# power_supply.net
KiCad netlist of a schematic drawn in EasyEDA Pro
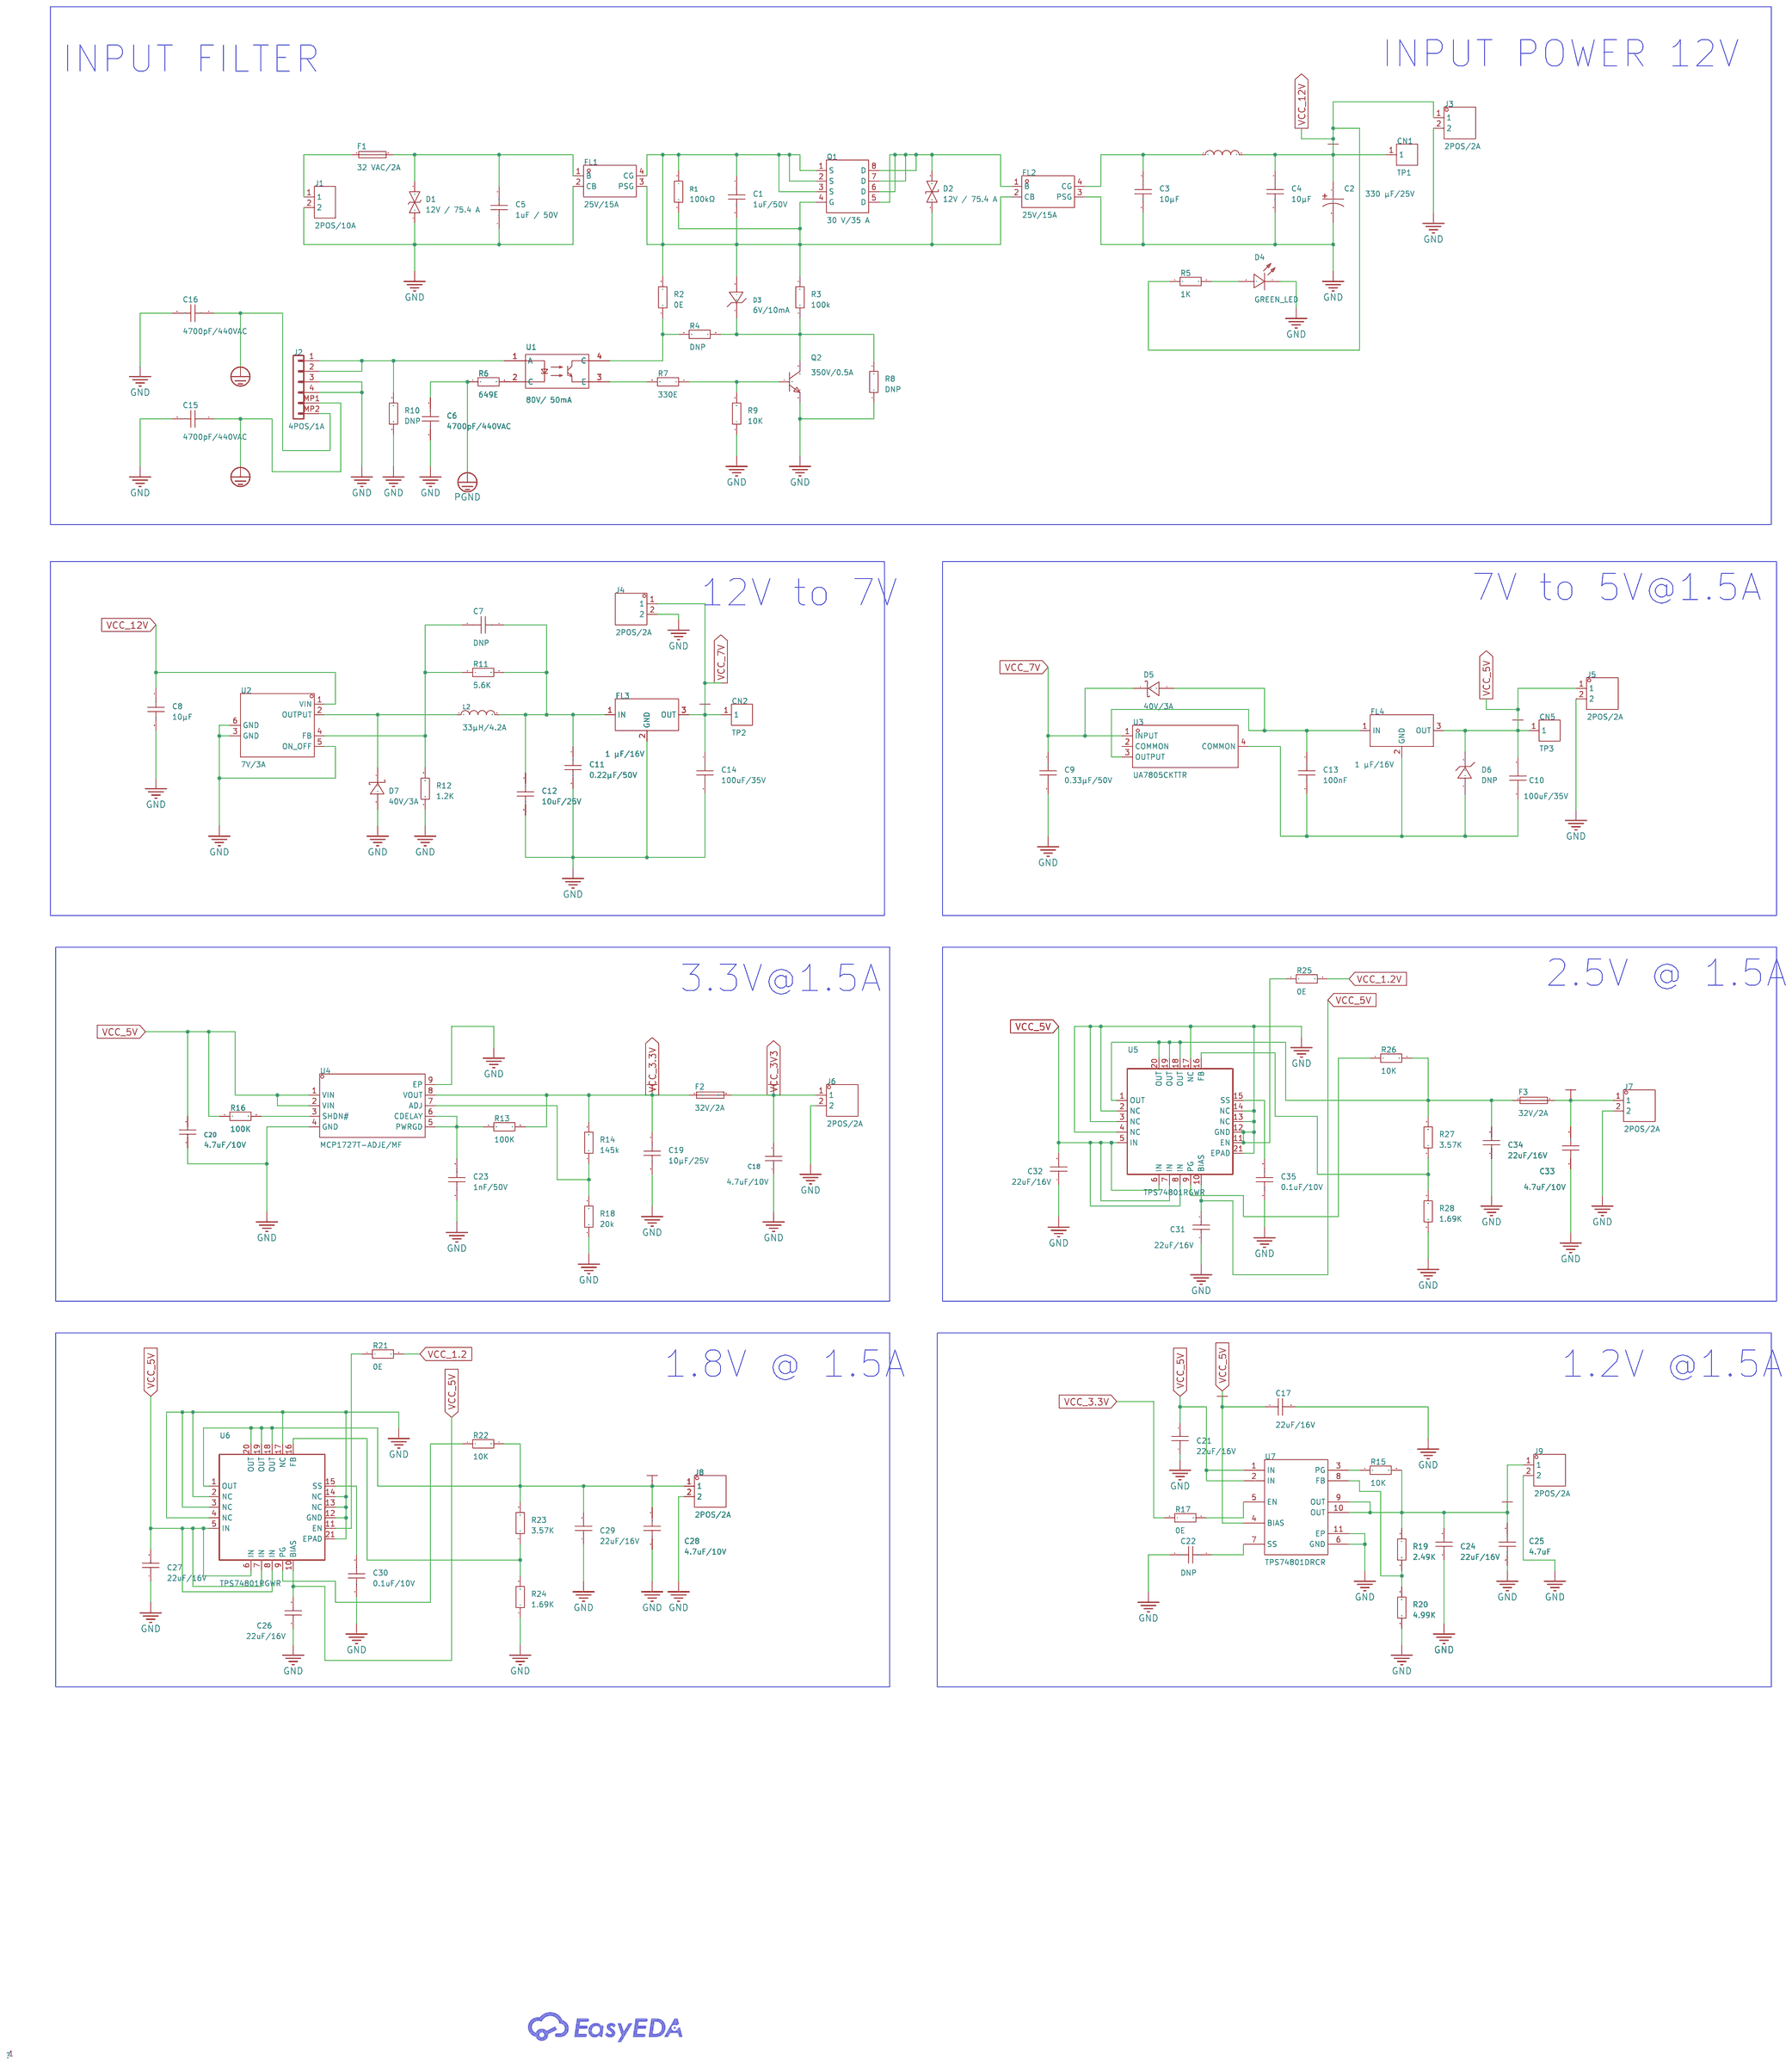
[diagram p0: schematic sheet]

(export (version "E")
  (design (tool "Eeschema 10.0.6"))
  (components
    (comp (ref "C1")
      (value "1uF/50V")
      (footprint "easyedapro:C0603")
      (libsource (lib "easyedapro") (part "CAP"))
    )
    (comp (ref "C2")
      (value "330 µF/25V")
      (footprint "easyedapro:CAP-SMD_BD10.0-L10.3-W10.3-FD")
      (fields (field (name "Manufacturer Part") "EEHZA1E331P") (field (name "Manufacturer") "PANASONIC(松下)"))
      (libsource (lib "easyedapro") (part "EEHZA1E331P"))
    )
    (comp (ref "C3")
      (value "10µF")
      (footprint "easyedapro:C0603")
      (libsource (lib "easyedapro") (part "CAP"))
    )
    (comp (ref "C4")
      (value "10µF")
      (footprint "easyedapro:C0603")
      (libsource (lib "easyedapro") (part "CAP"))
    )
    (comp (ref "C5")
      (value "1uF / 50V")
      (footprint "easyedapro:C0402")
      (description "Capacitance:100nF Tolerance:±10% Tolerance:±10% Voltage Rating:16V Temperature Coefficient:X7R")
      (fields
        (field (name "Manufacturer Part") "CL05B104KO5NNNC")
        (field (name "Manufacturer") "SAMSUNG(三星)")
      )
      (libsource (lib "easyedapro") (part "CL05B104KO5NNNC"))
    )
    (comp (ref "C6")
      (value "4700pF/440VAC")
      (footprint "easyedapro:CAP-TH_L11.0-W5.0-P10.00-D0.7")
      (fields
        (field (name "Manufacturer Part") "C947U472MZVDBA7317")
        (field (name "Manufacturer") "KEMET(基美)")
      )
      (libsource (lib "easyedapro") (part "C947U472MZVDBA7317"))
    )
    (comp (ref "C7") (value "DNP") (footprint "easyedapro:C0603") (libsource (lib "easyedapro") (part "CAP")))
    (comp (ref "C8")
      (value "10µF")
      (footprint "easyedapro:C0603")
      (libsource (lib "easyedapro") (part "CAP"))
    )
    (comp (ref "C9")
      (value "0.33µF/50V")
      (footprint "easyedapro:C0603")
      (libsource (lib "easyedapro") (part "CAP"))
    )
    (comp (ref "C10")
      (value "100uF/35V")
      (footprint "easyedapro:C0603")
      (libsource (lib "easyedapro") (part "CAP"))
    )
    (comp (ref "C11")
      (value "0.22µF/50V")
      (footprint "easyedapro:C0603")
      (libsource (lib "easyedapro") (part "CAP"))
    )
    (comp (ref "C12")
      (value "10uF/25V")
      (footprint "easyedapro:C0603")
      (libsource (lib "easyedapro") (part "CAP"))
    )
    (comp (ref "C13")
      (value "100nF")
      (footprint "easyedapro:C0603")
      (libsource (lib "easyedapro") (part "CAP"))
    )
    (comp (ref "C14")
      (value "100uF/35V")
      (footprint "easyedapro:C0603")
      (libsource (lib "easyedapro") (part "CAP"))
    )
    (comp (ref "C15")
      (value "4700pF/440VAC")
      (footprint "easyedapro:C0603")
      (libsource (lib "easyedapro") (part "CAP"))
    )
    (comp (ref "C16")
      (value "4700pF/440VAC")
      (footprint "easyedapro:C0603")
      (libsource (lib "easyedapro") (part "CAP"))
    )
    (comp (ref "C17")
      (value "22uF/16V")
      (footprint "easyedapro:C0805")
      (description "容值:22uF;精度:±20%;额定电压:16V;材质(温度系数):X5R;")
      (fields
        (field (name "Manufacturer Part") "CL21A226MOQNNNE")
        (field (name "Manufacturer") "SAMSUNG(三星)")
      )
      (libsource (lib "easyedapro") (part "CL21A226MOQNNNE"))
    )
    (comp (ref "C18")
      (value "4.7uF/10V")
      (footprint "easyedapro:C0603")
      (description "Capacitance:4.7uF Tolerance:±10% Tolerance:±10% Voltage Rating:10V Temperature Coefficient:X5R")
      (fields
        (field (name "Manufacturer Part") "CL10A475KP8NNNC")
        (field (name "Manufacturer") "SAMSUNG(三星)")
      )
      (libsource (lib "easyedapro") (part "CL10A475KP8NNNC"))
    )
    (comp (ref "C19")
      (value "10µF/25V")
      (footprint "easyedapro:C0603")
      (libsource (lib "easyedapro") (part "CAP"))
    )
    (comp (ref "C20")
      (value "4.7uF/10V")
      (footprint "easyedapro:C0603")
      (description "Capacitance:4.7uF Tolerance:±10% Tolerance:±10% Voltage Rating:10V Temperature Coefficient:X5R")
      (fields
        (field (name "Manufacturer Part") "CL10A475KP8NNNC")
        (field (name "Manufacturer") "SAMSUNG(三星)")
      )
      (libsource (lib "easyedapro") (part "CL10A475KP8NNNC"))
    )
    (comp (ref "C21")
      (value "22uF/16V")
      (footprint "easyedapro:C0805")
      (description "容值:22uF;精度:±20%;额定电压:16V;材质(温度系数):X5R;")
      (fields
        (field (name "Manufacturer Part") "CL21A226MOQNNNE")
        (field (name "Manufacturer") "SAMSUNG(三星)")
      )
      (libsource (lib "easyedapro") (part "CL21A226MOQNNNE"))
    )
    (comp (ref "C22")
      (value "DNP")
      (footprint "easyedapro:C0402")
      (fields
        (field (name "Manufacturer Part") "CC0402JRX7R6BB104")
        (field (name "Manufacturer") "YAGEO(国巨)")
      )
      (libsource (lib "easyedapro") (part "CC0402JRX7R6BB104"))
    )
    (comp (ref "C23")
      (value "1nF/50V")
      (footprint "easyedapro:C0402")
      (description "Capacitance:1nF Tolerance:±5% Tolerance:±5% Voltage Rating:50V Temperature Coefficient:C0G")
      (fields
        (field (name "Manufacturer Part") "GRM1555C1H102JA01D")
        (field (name "Manufacturer") "muRata(村田)")
      )
      (libsource (lib "easyedapro") (part "GRM1555C1H102JA01D"))
    )
    (comp (ref "C24")
      (value "22uF/16V")
      (footprint "easyedapro:C0805")
      (description "容值:22uF;精度:±20%;额定电压:16V;材质(温度系数):X5R;")
      (fields
        (field (name "Manufacturer Part") "CL21A226MOQNNNE")
        (field (name "Manufacturer") "SAMSUNG(三星)")
      )
      (libsource (lib "easyedapro") (part "CL21A226MOQNNNE"))
    )
    (comp (ref "C25")
      (value "4.7uF")
      (footprint "easyedapro:C0603")
      (libsource (lib "easyedapro") (part "CAP"))
    )
    (comp (ref "C26")
      (value "22uF/16V")
      (footprint "easyedapro:C0805")
      (description "容值:22uF;精度:±20%;额定电压:16V;材质(温度系数):X5R;")
      (fields
        (field (name "Manufacturer Part") "CL21A226MOQNNNE")
        (field (name "Manufacturer") "SAMSUNG(三星)")
      )
      (libsource (lib "easyedapro") (part "CL21A226MOQNNNE"))
    )
    (comp (ref "C27")
      (value "22uF/16V")
      (footprint "easyedapro:C0805")
      (description "容值:22uF;精度:±20%;额定电压:16V;材质(温度系数):X5R;")
      (fields
        (field (name "Manufacturer Part") "CL21A226MOQNNNE")
        (field (name "Manufacturer") "SAMSUNG(三星)")
      )
      (libsource (lib "easyedapro") (part "CL21A226MOQNNNE"))
    )
    (comp (ref "C28")
      (value "4.7uF/10V")
      (footprint "easyedapro:C0603")
      (libsource (lib "easyedapro") (part "CAP"))
    )
    (comp (ref "C29")
      (value "22uF/16V")
      (footprint "easyedapro:C0805")
      (description "容值:22uF;精度:±20%;额定电压:16V;材质(温度系数):X5R;")
      (fields
        (field (name "Manufacturer Part") "CL21A226MOQNNNE")
        (field (name "Manufacturer") "SAMSUNG(三星)")
      )
      (libsource (lib "easyedapro") (part "CL21A226MOQNNNE"))
    )
    (comp (ref "C30")
      (value "0.1uF/10V")
      (footprint "easyedapro:C0402")
      (fields
        (field (name "Manufacturer Part") "CC0402JRX7R6BB104")
        (field (name "Manufacturer") "YAGEO(国巨)")
      )
      (libsource (lib "easyedapro") (part "CC0402JRX7R6BB104"))
    )
    (comp (ref "C31")
      (value "22uF/16V")
      (footprint "easyedapro:C0805")
      (description "容值:22uF;精度:±20%;额定电压:16V;材质(温度系数):X5R;")
      (fields
        (field (name "Manufacturer Part") "CL21A226MOQNNNE")
        (field (name "Manufacturer") "SAMSUNG(三星)")
      )
      (libsource (lib "easyedapro") (part "CL21A226MOQNNNE"))
    )
    (comp (ref "C32")
      (value "22uF/16V")
      (footprint "easyedapro:C0805")
      (description "容值:22uF;精度:±20%;额定电压:16V;材质(温度系数):X5R;")
      (fields
        (field (name "Manufacturer Part") "CL21A226MOQNNNE")
        (field (name "Manufacturer") "SAMSUNG(三星)")
      )
      (libsource (lib "easyedapro") (part "CL21A226MOQNNNE"))
    )
    (comp (ref "C33")
      (value "4.7uF/10V")
      (footprint "easyedapro:C0603")
      (libsource (lib "easyedapro") (part "CAP"))
    )
    (comp (ref "C34")
      (value "22uF/16V")
      (footprint "easyedapro:C0805")
      (description "容值:22uF;精度:±20%;额定电压:16V;材质(温度系数):X5R;")
      (fields
        (field (name "Manufacturer Part") "CL21A226MOQNNNE")
        (field (name "Manufacturer") "SAMSUNG(三星)")
      )
      (libsource (lib "easyedapro") (part "CL21A226MOQNNNE"))
    )
    (comp (ref "C35")
      (value "0.1uF/10V")
      (footprint "easyedapro:C0402")
      (fields
        (field (name "Manufacturer Part") "CC0402JRX7R6BB104")
        (field (name "Manufacturer") "YAGEO(国巨)")
      )
      (libsource (lib "easyedapro") (part "CC0402JRX7R6BB104"))
    )
    (comp (ref "CN1")
      (value "TP1")
      (footprint "easyedapro:CONN-SMD_5017")
      (libsource (lib "easyedapro") (part "5017_C9900015874"))
    )
    (comp (ref "CN2")
      (value "TP2")
      (footprint "easyedapro:CONN-SMD_5017")
      (libsource (lib "easyedapro") (part "5017_C9900015874"))
    )
    (comp (ref "CN5")
      (value "TP3")
      (footprint "easyedapro:CONN-SMD_5017")
      (libsource (lib "easyedapro") (part "5017_C9900015874"))
    )
    (comp (ref "D1")
      (value "12V / 75.4 A")
      (footprint "easyedapro:D0402-BI")
      (fields (field (name "Manufacturer") "GOOD-ARK(固锝)"))
      (libsource (lib "easyedapro") (part "GSEPD15B0005"))
    )
    (comp (ref "D2")
      (value "12V / 75.4 A")
      (footprint "easyedapro:SMC_L6.9-W5.9-LS7.9-BI")
      (fields (field (name "Manufacturer") "R+O(宏嘉诚)"))
      (libsource (lib "easyedapro") (part "SMCJ12CA_C41411748"))
    )
    (comp (ref "D3")
      (value "6V/10mA")
      (footprint "easyedapro:SOD-123_L2.7-W1.6-LS3.7-RD")
      (fields (field (name "Manufacturer") "onsemi(安森美)"))
      (libsource (lib "easyedapro") (part "MMSZ5233BT1G"))
    )
    (comp (ref "D4")
      (value "GREEN_LED")
      (footprint "easyedapro:LED0603-RD")
      (fields (field (name "Manufacturer") "LITEON(光宝)"))
      (libsource (lib "easyedapro") (part "LTST-C190KGKT"))
    )
    (comp (ref "D5")
      (value "40V/3A")
      (footprint "easyedapro:SOD-128_L3.7-W2.5-LS4.7-RD")
      (fields (field (name "Manufacturer") "Nexperia(安世)"))
      (libsource (lib "easyedapro") (part "PMEG40T30EPX"))
    )
    (comp (ref "D6")
      (value "DNP")
      (footprint "easyedapro:SOD-123_L2.8-W1.8-LS3.7-RD")
      (fields (field (name "Manufacturer") "DIODES(美台)"))
      (libsource (lib "easyedapro") (part "MMSZ5231B-7-F"))
    )
    (comp (ref "D7")
      (value "40V/3A")
      (footprint "easyedapro:SOD-128_L3.7-W2.5-LS4.7-RD")
      (fields (field (name "Manufacturer") "Nexperia(安世)"))
      (libsource (lib "easyedapro") (part "PMEG40T30EPX"))
    )
    (comp (ref "F1")
      (value "32 VAC/2A")
      (footprint "easyedapro:FUSE-SMD_L20.0-W5.2")
      (fields (field (name "Manufacturer") "SET(赛尔特)"))
      (libsource (lib "easyedapro") (part "FUSE SGT520-8A"))
    )
    (comp (ref "F2")
      (value "32V/2A")
      (footprint "easyedapro:F0402")
      (fields (field (name "Manufacturer") "PANASONIC(松下)"))
      (libsource (lib "easyedapro") (part "ERBRD2R00X"))
    )
    (comp (ref "F3")
      (value "32V/2A")
      (footprint "easyedapro:F0402")
      (fields (field (name "Manufacturer") "PANASONIC(松下)"))
      (libsource (lib "easyedapro") (part "ERBRD2R00X"))
    )
    (comp (ref "FL1")
      (value "25V/15A")
      (footprint "easyedapro:FILTER-TH_6P-L12.0-W11.0_BNX016-01")
      (fields (field (name "Manufacturer Part") "BNX016-01") (field (name "Manufacturer") "muRata(村田)"))
      (libsource (lib "easyedapro") (part "BNX016-01"))
    )
    (comp (ref "FL2")
      (value "25V/15A")
      (footprint "easyedapro:FILTER-TH_6P-L12.0-W11.0_BNX016-01")
      (fields (field (name "Manufacturer Part") "BNX016-01") (field (name "Manufacturer") "muRata(村田)"))
      (libsource (lib "easyedapro") (part "BNX016-01"))
    )
    (comp (ref "FL3")
      (value "1 µF/16V")
      (footprint "easyedapro:FILTER-SMD_3P-L2.0-W1.2-L")
      (fields (field (name "Manufacturer") "muRata(村田)"))
      (libsource (lib "easyedapro") (part "NFM21PC105B1C3D"))
    )
    (comp (ref "FL4")
      (value "1 µF/16V")
      (footprint "easyedapro:FILTER-SMD_3P-L2.0-W1.2-L")
      (fields (field (name "Manufacturer") "muRata(村田)"))
      (libsource (lib "easyedapro") (part "NFM21PC105B1C3D"))
    )
    (comp (ref "J1")
      (value "2POS/10A")
      (footprint "easyedapro:CONN-TH_2P-P3.96-V")
      (fields (field (name "Manufacturer") "JST"))
      (libsource (lib "easyedapro") (part "B2P-VH-GZ"))
    )
    (comp (ref "J2")
      (value "Molex_PicoBlade_1x4_0533980471")
      (footprint "easyedapro:antmicro-footprints:Conn_Molex_PicoBlade_1x4_0533980471")
      (libsource (lib "easyedapro") (part "antmicroWire2BoardConnectors_Molex_PicoBlade_1x4_0533980471"))
    )
    (comp (ref "J3")
      (value "2POS/2A")
      (footprint "easyedapro:CONN-TH_S2B-PH-K-S-GW")
      (fields (field (name "Manufacturer") "JST"))
      (libsource (lib "easyedapro") (part "S2B-PH-K-S-GW"))
    )
    (comp (ref "J4")
      (value "2POS/2A")
      (footprint "easyedapro:CONN-TH_S2B-PH-K-S-GW")
      (fields (field (name "Manufacturer") "JST"))
      (libsource (lib "easyedapro") (part "S2B-PH-K-S-GW"))
    )
    (comp (ref "J5")
      (value "2POS/2A")
      (footprint "easyedapro:CONN-TH_S2B-PH-K-S-GW")
      (fields (field (name "Manufacturer") "JST"))
      (libsource (lib "easyedapro") (part "S2B-PH-K-S-GW"))
    )
    (comp (ref "J6")
      (value "2POS/2A")
      (footprint "easyedapro:CONN-TH_S2B-PH-K-S-GW")
      (fields (field (name "Manufacturer") "JST"))
      (libsource (lib "easyedapro") (part "S2B-PH-K-S-GW"))
    )
    (comp (ref "J7")
      (value "2POS/2A")
      (footprint "easyedapro:CONN-TH_S2B-PH-K-S-GW")
      (fields (field (name "Manufacturer") "JST"))
      (libsource (lib "easyedapro") (part "S2B-PH-K-S-GW"))
    )
    (comp (ref "J8")
      (value "2POS/2A")
      (footprint "easyedapro:CONN-TH_S2B-PH-K-S-GW")
      (fields (field (name "Manufacturer") "JST"))
      (libsource (lib "easyedapro") (part "S2B-PH-K-S-GW"))
    )
    (comp (ref "J9")
      (value "2POS/2A")
      (footprint "easyedapro:CONN-TH_S2B-PH-K-S-GW")
      (fields (field (name "Manufacturer") "JST"))
      (libsource (lib "easyedapro") (part "S2B-PH-K-S-GW"))
    )
    (comp (ref "L1")
      (value "22uH")
      (footprint "easyedapro:7447709220")
      (fields (field (name "Manufacturer Part") "22µH/5.3A") (field (name "Manufacturer") "WURTH"))
      (libsource (lib "easyedapro") (part "7447709220"))
    )
    (comp (ref "L2")
      (value "33µH/4.2A")
      (footprint "easyedapro:IND-SMD_L12.0-W12.0-A")
      (fields (field (name "Manufacturer Part") "7447709330") (field (name "Manufacturer") "Wurth(伍尔特)"))
      (libsource (lib "easyedapro") (part "7447709330"))
    )
    (comp (ref "Q1")
      (value "30 V/35 A")
      (footprint "easyedapro:POWERPAK-1212-8_L3.0-W3.0-P0.65-LS3.3-BL")
      (fields (field (name "Manufacturer") "MSKSEMI(美森科)"))
      (libsource (lib "easyedapro") (part "MSISH101DN-T1-GE3"))
    )
    (comp (ref "Q2")
      (value "350V/0.5A")
      (footprint "easyedapro:SOT-23-3_L2.9-W1.3-P1.90-LS2.4-BR")
      (fields (field (name "Manufacturer") "DIODES(美台)"))
      (libsource (lib "easyedapro") (part "FMMT6517TA"))
    )
    (comp (ref "R1")
      (value "100kΩ")
      (footprint "easyedapro:R0603")
      (fields (field (name "Manufacturer Part") "RC0603FR-07100KL") (field (name "Manufacturer") "YAGEO(国巨)"))
      (libsource (lib "easyedapro") (part "RC0603FR-07100KL"))
    )
    (comp (ref "R2") (value "0E") (footprint "easyedapro:R0603") (libsource (lib "easyedapro") (part "Res")))
    (comp (ref "R3")
      (value "100k")
      (footprint "easyedapro:R0603")
      (libsource (lib "easyedapro") (part "Res"))
    )
    (comp (ref "R4") (value "DNP") (footprint "easyedapro:R0603") (libsource (lib "easyedapro") (part "Res")))
    (comp (ref "R5") (value "1K") (footprint "easyedapro:R0603") (libsource (lib "easyedapro") (part "Res")))
    (comp (ref "R6")
      (value "649E")
      (footprint "easyedapro:R0603")
      (libsource (lib "easyedapro") (part "Res"))
    )
    (comp (ref "R7")
      (value "330E")
      (footprint "easyedapro:R0603")
      (libsource (lib "easyedapro") (part "Res"))
    )
    (comp (ref "R8") (value "DNP") (footprint "easyedapro:R0603") (libsource (lib "easyedapro") (part "Res")))
    (comp (ref "R9") (value "10K") (footprint "easyedapro:R0603") (libsource (lib "easyedapro") (part "Res")))
    (comp (ref "R10")
      (value "DNP")
      (footprint "easyedapro:R0603")
      (libsource (lib "easyedapro") (part "Res"))
    )
    (comp (ref "R11")
      (value "5.6K")
      (footprint "easyedapro:R0603")
      (libsource (lib "easyedapro") (part "Res"))
    )
    (comp (ref "R12")
      (value "1.2K")
      (footprint "easyedapro:R0603")
      (libsource (lib "easyedapro") (part "Res"))
    )
    (comp (ref "R13")
      (value "100K")
      (footprint "easyedapro:R0402")
      (fields (field (name "Manufacturer Part") "ERJ2RKF1003X") (field (name "Manufacturer") "PANASONIC(松下)"))
      (libsource (lib "easyedapro") (part "ERJ-2RKF1003X"))
    )
    (comp (ref "R14")
      (value "145k")
      (footprint "easyedapro:R0603")
      (libsource (lib "easyedapro") (part "Res"))
    )
    (comp (ref "R15")
      (value "10K")
      (footprint "easyedapro:R0603")
      (libsource (lib "easyedapro") (part "Res"))
    )
    (comp (ref "R16")
      (value "100K")
      (footprint "easyedapro:R0402")
      (fields (field (name "Manufacturer Part") "ERJ2RKF1003X") (field (name "Manufacturer") "PANASONIC(松下)"))
      (libsource (lib "easyedapro") (part "ERJ-2RKF1003X"))
    )
    (comp (ref "R17") (value "0E") (footprint "easyedapro:R0603") (libsource (lib "easyedapro") (part "Res")))
    (comp (ref "R18")
      (value "20k")
      (footprint "easyedapro:R0603")
      (libsource (lib "easyedapro") (part "Res"))
    )
    (comp (ref "R19")
      (value "2.49K")
      (footprint "easyedapro:R0603")
      (libsource (lib "easyedapro") (part "Res"))
    )
    (comp (ref "R20")
      (value "4.99K")
      (footprint "easyedapro:R0603")
      (libsource (lib "easyedapro") (part "Res"))
    )
    (comp (ref "R21") (value "0E") (footprint "easyedapro:R0603") (libsource (lib "easyedapro") (part "Res")))
    (comp (ref "R22")
      (value "10K")
      (footprint "easyedapro:R0603")
      (libsource (lib "easyedapro") (part "Res"))
    )
    (comp (ref "R23")
      (value "3.57K")
      (footprint "easyedapro:R0603")
      (libsource (lib "easyedapro") (part "Res"))
    )
    (comp (ref "R24")
      (value "1.69K")
      (footprint "easyedapro:R0603")
      (libsource (lib "easyedapro") (part "Res"))
    )
    (comp (ref "R25") (value "0E") (footprint "easyedapro:R0603") (libsource (lib "easyedapro") (part "Res")))
    (comp (ref "R26")
      (value "10K")
      (footprint "easyedapro:R0603")
      (libsource (lib "easyedapro") (part "Res"))
    )
    (comp (ref "R27")
      (value "3.57K")
      (footprint "easyedapro:R0603")
      (libsource (lib "easyedapro") (part "Res"))
    )
    (comp (ref "R28")
      (value "1.69K")
      (footprint "easyedapro:R0603")
      (libsource (lib "easyedapro") (part "Res"))
    )
    (comp (ref "U1")
      (value "80V/ 50mA")
      (footprint "easyedapro:SOP-4_L6.5-W4.6-P2.54-LS10.3-TL")
      (fields (field (name "Manufacturer") "VISHAY(威世)"))
      (libsource (lib "easyedapro") (part "VO617A-8X017T"))
    )
    (comp (ref "U2")
      (value "7V/3A")
      (footprint "easyedapro:TO-263-5_L10.4-W8.6-P1.70-LS15.3-BR")
      (libsource (lib "easyedapro") (part "LM2596S-ADJ_C3198435"))
    )
    (comp (ref "U3")
      (value "UA7805CKTTR")
      (footprint "easyedapro:TO-263-3_L10.2-W9.0-P2.54-LS15.2-TL")
      (fields (field (name "Manufacturer") "TI(德州仪器)"))
      (libsource (lib "easyedapro") (part "UA7805CKTTR"))
    )
    (comp (ref "U4")
      (value "MCP1727T-ADJE/MF")
      (footprint "easyedapro:DFN-8_L3.0-W3.0-P0.65-BL-EP")
      (fields (field (name "Manufacturer") "MICROCHIP(美国微芯)"))
      (libsource (lib "easyedapro") (part "MCP1727T-ADJE/MF"))
    )
    (comp (ref "U5")
      (value "TPS74801RGWR")
      (footprint "easyedapro:VQFN-20_L5.0-W5.0-P0.65-TL-EP")
      (fields (field (name "Manufacturer") "Texas Instruments"))
      (libsource (lib "easyedapro") (part "TPS74801RGWR"))
    )
    (comp (ref "U6")
      (value "TPS74801RGWR")
      (footprint "easyedapro:VQFN-20_L5.0-W5.0-P0.65-TL-EP")
      (fields (field (name "Manufacturer") "Texas Instruments"))
      (libsource (lib "easyedapro") (part "TPS74801RGWR"))
    )
    (comp (ref "U7")
      (value "TPS74801DRCR")
      (footprint "easyedapro:VSON-10_L3.0-W3.0-P0.50-TL-EP")
      (fields (field (name "Manufacturer") "TI(德州仪器)"))
      (libsource (lib "easyedapro") (part "TPS74801DRCR"))
    )
  )
  (nets
    (net (code "1") (name "GND") (class "Default")
      (node (ref "C11") (pin "2") (pinfunction "2_2") (pintype "input"))
      (node (ref "C12") (pin "2") (pinfunction "2_2") (pintype "input"))
      (node (ref "C14") (pin "2") (pinfunction "2_2") (pintype "input"))
      (node (ref "C15") (pin "2") (pinfunction "2_2") (pintype "input"))
      (node (ref "C16") (pin "2") (pinfunction "2_2") (pintype "input"))
      (node (ref "C17") (pin "2") (pinfunction "2_2") (pintype "input"))
      (node (ref "C18") (pin "1") (pinfunction "1_1") (pintype "input"))
      (node (ref "C19") (pin "2") (pinfunction "2_2") (pintype "input"))
      (node (ref "C2") (pin "2") (pinfunction "2_2") (pintype "unspecified"))
      (node (ref "C20") (pin "1") (pinfunction "1_1") (pintype "input"))
      (node (ref "C21") (pin "1") (pinfunction "1_1") (pintype "input"))
      (node (ref "C22") (pin "1") (pinfunction "1_1") (pintype "input"))
      (node (ref "C23") (pin "1") (pinfunction "1_1") (pintype "unspecified"))
      (node (ref "C24") (pin "1") (pinfunction "1_1") (pintype "input"))
      (node (ref "C25") (pin "2") (pinfunction "2_2") (pintype "input"))
      (node (ref "C26") (pin "1") (pinfunction "1_1") (pintype "input"))
      (node (ref "C27") (pin "1") (pinfunction "1_1") (pintype "input"))
      (node (ref "C28") (pin "2") (pinfunction "2_2") (pintype "input"))
      (node (ref "C29") (pin "1") (pinfunction "1_1") (pintype "input"))
      (node (ref "C3") (pin "2") (pinfunction "2_2") (pintype "input"))
      (node (ref "C30") (pin "1") (pinfunction "1_1") (pintype "input"))
      (node (ref "C31") (pin "1") (pinfunction "1_1") (pintype "input"))
      (node (ref "C32") (pin "1") (pinfunction "1_1") (pintype "input"))
      (node (ref "C33") (pin "2") (pinfunction "2_2") (pintype "input"))
      (node (ref "C34") (pin "1") (pinfunction "1_1") (pintype "input"))
      (node (ref "C35") (pin "1") (pinfunction "1_1") (pintype "input"))
      (node (ref "C4") (pin "2") (pinfunction "2_2") (pintype "input"))
      (node (ref "C5") (pin "1") (pinfunction "1_1") (pintype "unspecified"))
      (node (ref "C6") (pin "1") (pinfunction "1_1") (pintype "unspecified"))
      (node (ref "C8") (pin "2") (pinfunction "2_2") (pintype "input"))
      (node (ref "C9") (pin "2") (pinfunction "2_2") (pintype "input"))
      (node (ref "D1") (pin "1") (pinfunction "1_1") (pintype "unspecified"))
      (node (ref "D4") (pin "1") (pinfunction "-_1") (pintype "unspecified"))
      (node (ref "D7") (pin "2") (pinfunction "A_2") (pintype "unspecified"))
      (node (ref "FL1") (pin "2") (pinfunction "CB_2") (pintype "input"))
      (node (ref "FL2") (pin "3") (pinfunction "PSG_3") (pintype "input"))
      (node (ref "FL3") (pin "2") (pinfunction "GND_2") (pintype "unspecified"))
      (node (ref "J1") (pin "2") (pinfunction "2_2") (pintype "unspecified"))
      (node (ref "J2") (pin "3") (pinfunction "3_3") (pintype "unspecified"))
      (node (ref "J2") (pin "4") (pinfunction "4_4") (pintype "unspecified"))
      (node (ref "J3") (pin "2") (pinfunction "2_2") (pintype "unspecified"))
      (node (ref "J4") (pin "2") (pinfunction "2_2") (pintype "unspecified"))
      (node (ref "J5") (pin "2") (pinfunction "2_2") (pintype "unspecified"))
      (node (ref "J6") (pin "2") (pinfunction "2_2") (pintype "unspecified"))
      (node (ref "J7") (pin "2") (pinfunction "2_2") (pintype "unspecified"))
      (node (ref "J8") (pin "2") (pinfunction "2_2") (pintype "unspecified"))
      (node (ref "J9") (pin "2") (pinfunction "2_2") (pintype "unspecified"))
      (node (ref "Q2") (pin "2") (pinfunction "E_2") (pintype "unspecified"))
      (node (ref "R10") (pin "1") (pinfunction "1_1") (pintype "input"))
      (node (ref "R12") (pin "1") (pinfunction "1_1") (pintype "input"))
      (node (ref "R18") (pin "1") (pinfunction "1_1") (pintype "input"))
      (node (ref "R20") (pin "1") (pinfunction "1_1") (pintype "input"))
      (node (ref "R24") (pin "1") (pinfunction "1_1") (pintype "input"))
      (node (ref "R25") (pin "1") (pinfunction "1_1") (pintype "input"))
      (node (ref "R28") (pin "1") (pinfunction "1_1") (pintype "input"))
      (node (ref "R8") (pin "1") (pinfunction "1_1") (pintype "input"))
      (node (ref "R9") (pin "1") (pinfunction "1_1") (pintype "input"))
      (node (ref "U2") (pin "3") (pinfunction "GND_3") (pintype "unspecified"))
      (node (ref "U2") (pin "5") (pinfunction "ON_OFF_5") (pintype "unspecified"))
      (node (ref "U2") (pin "6") (pinfunction "GND_6") (pintype "unspecified"))
      (node (ref "U4") (pin "4") (pinfunction "GND_4") (pintype "unspecified"))
      (node (ref "U4") (pin "9") (pinfunction "EP_9") (pintype "unspecified"))
      (node (ref "U5") (pin "11") (pinfunction "EN_11") (pintype "unspecified"))
      (node (ref "U5") (pin "12") (pinfunction "GND_12") (pintype "unspecified"))
      (node (ref "U5") (pin "13") (pinfunction "NC_13") (pintype "unspecified"))
      (node (ref "U5") (pin "14") (pinfunction "NC_14") (pintype "unspecified"))
      (node (ref "U5") (pin "17") (pinfunction "NC_17") (pintype "unspecified"))
      (node (ref "U5") (pin "2") (pinfunction "NC_2") (pintype "unspecified"))
      (node (ref "U5") (pin "21") (pinfunction "EPAD_21") (pintype "unspecified"))
      (node (ref "U5") (pin "3") (pinfunction "NC_3") (pintype "unspecified"))
      (node (ref "U5") (pin "4") (pinfunction "NC_4") (pintype "unspecified"))
      (node (ref "U6") (pin "12") (pinfunction "GND_12") (pintype "unspecified"))
      (node (ref "U6") (pin "13") (pinfunction "NC_13") (pintype "unspecified"))
      (node (ref "U6") (pin "14") (pinfunction "NC_14") (pintype "unspecified"))
      (node (ref "U6") (pin "17") (pinfunction "NC_17") (pintype "unspecified"))
      (node (ref "U6") (pin "2") (pinfunction "NC_2") (pintype "unspecified"))
      (node (ref "U6") (pin "21") (pinfunction "EPAD_21") (pintype "unspecified"))
      (node (ref "U6") (pin "3") (pinfunction "NC_3") (pintype "unspecified"))
      (node (ref "U6") (pin "4") (pinfunction "NC_4") (pintype "unspecified"))
      (node (ref "U7") (pin "11") (pinfunction "EP_11") (pintype "unspecified"))
      (node (ref "U7") (pin "6") (pinfunction "GND_6") (pintype "unspecified"))
    )
    (net (code "2") (name "ISO_GND") (class "Default")
      (node (ref "C15") (pin "1") (pinfunction "1_1") (pintype "input"))
      (node (ref "C16") (pin "1") (pinfunction "1_1") (pintype "input"))
      (node (ref "J2") (pin "MP1") (pinfunction "MP1_MP1") (pintype "unspecified"))
      (node (ref "J2") (pin "MP2") (pinfunction "MP2_MP2") (pintype "unspecified"))
    )
    (net (code "3") (name "Net-(C34-Pad2)") (class "Default")
      (node (ref "C34") (pin "2") (pinfunction "2_2") (pintype "input"))
      (node (ref "F3") (pin "1") (pinfunction "1_1") (pintype "input"))
      (node (ref "R26") (pin "2") (pinfunction "2_2") (pintype "input"))
      (node (ref "R27") (pin "2") (pinfunction "2_2") (pintype "input"))
      (node (ref "U5") (pin "1") (pinfunction "OUT_1") (pintype "unspecified"))
      (node (ref "U5") (pin "18") (pinfunction "OUT_18") (pintype "unspecified"))
      (node (ref "U5") (pin "19") (pinfunction "OUT_19") (pintype "unspecified"))
      (node (ref "U5") (pin "20") (pinfunction "OUT_20") (pintype "unspecified"))
    )
    (net (code "4") (name "Net-(D3-A)") (class "Default")
      (node (ref "C1") (pin "1") (pinfunction "1_1") (pintype "input"))
      (node (ref "C1") (pin "2") (pinfunction "2_2") (pintype "input"))
      (node (ref "D2") (pin "1") (pinfunction "1_1") (pintype "unspecified"))
      (node (ref "D3") (pin "2") (pinfunction "A_2") (pintype "input"))
      (node (ref "FL1") (pin "3") (pinfunction "PSG_3") (pintype "input"))
      (node (ref "FL1") (pin "4") (pinfunction "CG_4") (pintype "input"))
      (node (ref "FL2") (pin "2") (pinfunction "CB_2") (pintype "input"))
      (node (ref "Q1") (pin "1") (pinfunction "S_1") (pintype "unspecified"))
      (node (ref "Q1") (pin "2") (pinfunction "S_2") (pintype "unspecified"))
      (node (ref "Q1") (pin "3") (pinfunction "S_3") (pintype "unspecified"))
      (node (ref "Q1") (pin "4") (pinfunction "G_4") (pintype "unspecified"))
      (node (ref "R1") (pin "1") (pinfunction "1_1") (pintype "input"))
      (node (ref "R1") (pin "2") (pinfunction "2_2") (pintype "input"))
      (node (ref "R2") (pin "2") (pinfunction "2_2") (pintype "input"))
      (node (ref "R3") (pin "2") (pinfunction "2_2") (pintype "input"))
    )
    (net (code "5") (name "Net-(D3-C)") (class "Default")
      (node (ref "D3") (pin "1") (pinfunction "C_1") (pintype "input"))
      (node (ref "Q2") (pin "3") (pinfunction "C_3") (pintype "unspecified"))
      (node (ref "R3") (pin "1") (pinfunction "1_1") (pintype "input"))
      (node (ref "R4") (pin "2") (pinfunction "2_2") (pintype "input"))
      (node (ref "R8") (pin "2") (pinfunction "2_2") (pintype "input"))
    )
    (net (code "6") (name "Net-(D4-+)") (class "Default")
      (node (ref "D4") (pin "2") (pinfunction "+_2") (pintype "unspecified"))
      (node (ref "R5") (pin "2") (pinfunction "2_2") (pintype "input"))
    )
    (net (code "7") (name "Net-(D5-A)") (class "Default")
      (node (ref "C13") (pin "1") (pinfunction "1_1") (pintype "input"))
      (node (ref "D5") (pin "2") (pinfunction "A_2") (pintype "unspecified"))
      (node (ref "FL4") (pin "1") (pinfunction "IN_1") (pintype "unspecified"))
      (node (ref "U3") (pin "3") (pinfunction "OUTPUT_3") (pintype "unspecified"))
    )
    (net (code "8") (name "Net-(D6-A)") (class "Default")
      (node (ref "C10") (pin "2") (pinfunction "2_2") (pintype "input"))
      (node (ref "C13") (pin "2") (pinfunction "2_2") (pintype "input"))
      (node (ref "D6") (pin "2") (pinfunction "A_2") (pintype "input"))
      (node (ref "FL4") (pin "2") (pinfunction "GND_2") (pintype "unspecified"))
      (node (ref "U3") (pin "4") (pinfunction "COMMON_4") (pintype "unspecified"))
    )
    (net (code "9") (name "Net-(D7-C)") (class "Default")
      (node (ref "D7") (pin "1") (pinfunction "C_1") (pintype "unspecified"))
      (node (ref "L2") (pin "1") (pinfunction "1_1") (pintype "input"))
      (node (ref "U2") (pin "2") (pinfunction "OUTPUT_2") (pintype "unspecified"))
    )
    (net (code "10") (name "Net-(F1-Pad1)") (class "Default")
      (node (ref "F1") (pin "1") (pinfunction "1_1") (pintype "unspecified"))
      (node (ref "J1") (pin "1") (pinfunction "1_1") (pintype "unspecified"))
    )
    (net (code "11") (name "Net-(FL1-B)") (class "Default")
      (node (ref "C5") (pin "2") (pinfunction "2_2") (pintype "unspecified"))
      (node (ref "D1") (pin "2") (pinfunction "2_2") (pintype "unspecified"))
      (node (ref "F1") (pin "2") (pinfunction "2_2") (pintype "unspecified"))
      (node (ref "FL1") (pin "1") (pinfunction "B_1") (pintype "input"))
    )
    (net (code "12") (name "Net-(FL2-B)") (class "Default")
      (node (ref "D2") (pin "2") (pinfunction "2_2") (pintype "unspecified"))
      (node (ref "FL2") (pin "1") (pinfunction "B_1") (pintype "input"))
      (node (ref "Q1") (pin "5") (pinfunction "D_5") (pintype "unspecified"))
      (node (ref "Q1") (pin "6") (pinfunction "D_6") (pintype "unspecified"))
      (node (ref "Q1") (pin "7") (pinfunction "D_7") (pintype "unspecified"))
      (node (ref "Q1") (pin "8") (pinfunction "D_8") (pintype "unspecified"))
    )
    (net (code "13") (name "Net-(FL2-CG)") (class "Default")
      (node (ref "C3") (pin "1") (pinfunction "1_1") (pintype "input"))
      (node (ref "FL2") (pin "4") (pinfunction "CG_4") (pintype "input"))
      (node (ref "L1") (pin "1") (pinfunction "1_1") (pintype "unspecified"))
    )
    (net (code "14") (name "Net-(FL3-IN)") (class "Default")
      (node (ref "C11") (pin "1") (pinfunction "1_1") (pintype "input"))
      (node (ref "C12") (pin "1") (pinfunction "1_1") (pintype "input"))
      (node (ref "C7") (pin "1") (pinfunction "1_1") (pintype "input"))
      (node (ref "FL3") (pin "1") (pinfunction "IN_1") (pintype "unspecified"))
      (node (ref "L2") (pin "2") (pinfunction "2_2") (pintype "input"))
      (node (ref "R11") (pin "2") (pinfunction "2_2") (pintype "input"))
    )
    (net (code "15") (name "Net-(Q2-B)") (class "Default")
      (node (ref "Q2") (pin "1") (pinfunction "B_1") (pintype "unspecified"))
      (node (ref "R7") (pin "1") (pinfunction "1_1") (pintype "input"))
      (node (ref "R9") (pin "2") (pinfunction "2_2") (pintype "input"))
    )
    (net (code "16") (name "Net-(R2-Pad1)") (class "Default")
      (node (ref "R2") (pin "1") (pinfunction "1_1") (pintype "input"))
      (node (ref "R4") (pin "1") (pinfunction "1_1") (pintype "input"))
      (node (ref "U1") (pin "4") (pinfunction "C_4") (pintype "unspecified"))
    )
    (net (code "17") (name "Net-(R6-Pad2)") (class "Default")
      (node (ref "R6") (pin "2") (pinfunction "2_2") (pintype "input"))
      (node (ref "U1") (pin "2") (pinfunction "C_2") (pintype "unspecified"))
    )
    (net (code "18") (name "Net-(U1-A)") (class "Default")
      (node (ref "J2") (pin "1") (pinfunction "1_1") (pintype "unspecified"))
      (node (ref "J2") (pin "2") (pinfunction "2_2") (pintype "unspecified"))
      (node (ref "R10") (pin "2") (pinfunction "2_2") (pintype "input"))
      (node (ref "U1") (pin "1") (pinfunction "A_1") (pintype "unspecified"))
    )
    (net (code "19") (name "Net-(U1-E)") (class "Default")
      (node (ref "R7") (pin "2") (pinfunction "2_2") (pintype "input"))
      (node (ref "U1") (pin "3") (pinfunction "E_3") (pintype "unspecified"))
    )
    (net (code "20") (name "Net-(U2-FB)") (class "Default")
      (node (ref "C7") (pin "2") (pinfunction "2_2") (pintype "input"))
      (node (ref "R11") (pin "1") (pinfunction "1_1") (pintype "input"))
      (node (ref "R12") (pin "2") (pinfunction "2_2") (pintype "input"))
      (node (ref "U2") (pin "4") (pinfunction "FB_4") (pintype "unspecified"))
    )
    (net (code "21") (name "Net-(U4-ADJ)") (class "Default")
      (node (ref "R14") (pin "1") (pinfunction "1_1") (pintype "input"))
      (node (ref "R18") (pin "2") (pinfunction "2_2") (pintype "input"))
      (node (ref "U4") (pin "7") (pinfunction "ADJ_7") (pintype "unspecified"))
    )
    (net (code "22") (name "Net-(U4-CDELAY)") (class "Default")
      (node (ref "C23") (pin "2") (pinfunction "2_2") (pintype "unspecified"))
      (node (ref "R13") (pin "1") (pinfunction "1_1") (pintype "unspecified"))
      (node (ref "U4") (pin "5") (pinfunction "PWRGD_5") (pintype "unspecified"))
      (node (ref "U4") (pin "6") (pinfunction "CDELAY_6") (pintype "unspecified"))
    )
    (net (code "23") (name "Net-(U4-SHDN#)") (class "Default")
      (node (ref "R16") (pin "2") (pinfunction "2_2") (pintype "unspecified"))
      (node (ref "U4") (pin "3") (pinfunction "SHDN#_3") (pintype "unspecified"))
    )
    (net (code "24") (name "Net-(U5-FB)") (class "Default")
      (node (ref "R27") (pin "1") (pinfunction "1_1") (pintype "input"))
      (node (ref "R28") (pin "2") (pinfunction "2_2") (pintype "input"))
      (node (ref "U5") (pin "16") (pinfunction "FB_16") (pintype "unspecified"))
    )
    (net (code "25") (name "Net-(U5-PG)") (class "Default")
      (node (ref "R26") (pin "1") (pinfunction "1_1") (pintype "input"))
      (node (ref "U5") (pin "9") (pinfunction "PG_9") (pintype "unspecified"))
    )
    (net (code "26") (name "Net-(U5-SS)") (class "Default")
      (node (ref "C35") (pin "2") (pinfunction "2_2") (pintype "input"))
      (node (ref "U5") (pin "15") (pinfunction "SS_15") (pintype "unspecified"))
    )
    (net (code "27") (name "Net-(U6-EN)") (class "Default")
      (node (ref "R21") (pin "1") (pinfunction "1_1") (pintype "input"))
      (node (ref "U6") (pin "11") (pinfunction "EN_11") (pintype "unspecified"))
    )
    (net (code "28") (name "Net-(U6-FB)") (class "Default")
      (node (ref "R23") (pin "1") (pinfunction "1_1") (pintype "input"))
      (node (ref "R24") (pin "2") (pinfunction "2_2") (pintype "input"))
      (node (ref "U6") (pin "16") (pinfunction "FB_16") (pintype "unspecified"))
    )
    (net (code "29") (name "Net-(U6-PG)") (class "Default")
      (node (ref "R22") (pin "1") (pinfunction "1_1") (pintype "input"))
      (node (ref "U6") (pin "9") (pinfunction "PG_9") (pintype "unspecified"))
    )
    (net (code "30") (name "Net-(U6-SS)") (class "Default")
      (node (ref "C30") (pin "2") (pinfunction "2_2") (pintype "input"))
      (node (ref "U6") (pin "15") (pinfunction "SS_15") (pintype "unspecified"))
    )
    (net (code "31") (name "Net-(U7-EN)") (class "Default")
      (node (ref "R17") (pin "2") (pinfunction "2_2") (pintype "input"))
      (node (ref "U7") (pin "5") (pinfunction "EN_5") (pintype "unspecified"))
    )
    (net (code "32") (name "Net-(U7-FB)") (class "Default")
      (node (ref "R19") (pin "1") (pinfunction "1_1") (pintype "input"))
      (node (ref "R20") (pin "2") (pinfunction "2_2") (pintype "input"))
      (node (ref "U7") (pin "8") (pinfunction "FB_8") (pintype "unspecified"))
    )
    (net (code "33") (name "Net-(U7-PG)") (class "Default")
      (node (ref "R15") (pin "1") (pinfunction "1_1") (pintype "input"))
      (node (ref "U7") (pin "3") (pinfunction "PG_3") (pintype "unspecified"))
    )
    (net (code "34") (name "Net-(U7-SS)") (class "Default")
      (node (ref "C22") (pin "2") (pinfunction "2_2") (pintype "input"))
      (node (ref "U7") (pin "7") (pinfunction "SS_7") (pintype "unspecified"))
    )
    (net (code "35") (name "PGND") (class "Default")
      (node (ref "C6") (pin "2") (pinfunction "2_2") (pintype "unspecified"))
      (node (ref "R6") (pin "1") (pinfunction "1_1") (pintype "input"))
    )
    (net (code "36") (name "VCC_1.2") (class "Default")
      (node (ref "R21") (pin "2") (pinfunction "2_2") (pintype "input"))
    )
    (net (code "37") (name "VCC_1.2V") (class "Default")
      (node (ref "C24") (pin "2") (pinfunction "2_2") (pintype "input"))
      (node (ref "C25") (pin "1") (pinfunction "1_1") (pintype "input"))
      (node (ref "J9") (pin "1") (pinfunction "1_1") (pintype "unspecified"))
      (node (ref "R15") (pin "2") (pinfunction "2_2") (pintype "input"))
      (node (ref "R19") (pin "2") (pinfunction "2_2") (pintype "input"))
      (node (ref "R25") (pin "2") (pinfunction "2_2") (pintype "input"))
      (node (ref "U7") (pin "10") (pinfunction "OUT_10") (pintype "unspecified"))
      (node (ref "U7") (pin "9") (pinfunction "OUT_9") (pintype "unspecified"))
    )
    (net (code "38") (name "VCC_1.8V") (class "Default")
      (node (ref "C28") (pin "1") (pinfunction "1_1") (pintype "input"))
      (node (ref "C29") (pin "2") (pinfunction "2_2") (pintype "input"))
      (node (ref "J8") (pin "1") (pinfunction "1_1") (pintype "unspecified"))
      (node (ref "R22") (pin "2") (pinfunction "2_2") (pintype "input"))
      (node (ref "R23") (pin "2") (pinfunction "2_2") (pintype "input"))
      (node (ref "U6") (pin "1") (pinfunction "OUT_1") (pintype "unspecified"))
      (node (ref "U6") (pin "18") (pinfunction "OUT_18") (pintype "unspecified"))
      (node (ref "U6") (pin "19") (pinfunction "OUT_19") (pintype "unspecified"))
      (node (ref "U6") (pin "20") (pinfunction "OUT_20") (pintype "unspecified"))
    )
    (net (code "39") (name "VCC_2.5V") (class "Default")
      (node (ref "C33") (pin "1") (pinfunction "1_1") (pintype "input"))
      (node (ref "F3") (pin "2") (pinfunction "2_2") (pintype "input"))
      (node (ref "J7") (pin "1") (pinfunction "1_1") (pintype "unspecified"))
    )
    (net (code "40") (name "VCC_3.3V") (class "Default")
      (node (ref "C19") (pin "1") (pinfunction "1_1") (pintype "input"))
      (node (ref "F2") (pin "1") (pinfunction "1_1") (pintype "input"))
      (node (ref "R13") (pin "2") (pinfunction "2_2") (pintype "unspecified"))
      (node (ref "R14") (pin "2") (pinfunction "2_2") (pintype "input"))
      (node (ref "R17") (pin "1") (pinfunction "1_1") (pintype "input"))
      (node (ref "U4") (pin "8") (pinfunction "VOUT_8") (pintype "unspecified"))
    )
    (net (code "41") (name "VCC_3V3") (class "Default")
      (node (ref "C18") (pin "2") (pinfunction "2_2") (pintype "input"))
      (node (ref "F2") (pin "2") (pinfunction "2_2") (pintype "input"))
      (node (ref "J6") (pin "1") (pinfunction "1_1") (pintype "unspecified"))
    )
    (net (code "42") (name "VCC_5V") (class "Default")
      (node (ref "C10") (pin "1") (pinfunction "1_1") (pintype "input"))
      (node (ref "C17") (pin "1") (pinfunction "1_1") (pintype "input"))
      (node (ref "C20") (pin "2") (pinfunction "2_2") (pintype "input"))
      (node (ref "C21") (pin "2") (pinfunction "2_2") (pintype "input"))
      (node (ref "C26") (pin "2") (pinfunction "2_2") (pintype "input"))
      (node (ref "C27") (pin "2") (pinfunction "2_2") (pintype "input"))
      (node (ref "C31") (pin "2") (pinfunction "2_2") (pintype "input"))
      (node (ref "C32") (pin "2") (pinfunction "2_2") (pintype "input"))
      (node (ref "CN5") (pin "1") (pinfunction "1_1") (pintype "unspecified"))
      (node (ref "D6") (pin "1") (pinfunction "K_1") (pintype "input"))
      (node (ref "FL4") (pin "3") (pinfunction "OUT_3") (pintype "unspecified"))
      (node (ref "J5") (pin "1") (pinfunction "1_1") (pintype "unspecified"))
      (node (ref "R16") (pin "1") (pinfunction "1_1") (pintype "unspecified"))
      (node (ref "U4") (pin "1") (pinfunction "VIN_1") (pintype "unspecified"))
      (node (ref "U4") (pin "2") (pinfunction "VIN_2") (pintype "unspecified"))
      (node (ref "U5") (pin "10") (pinfunction "BIAS_10") (pintype "unspecified"))
      (node (ref "U5") (pin "5") (pinfunction "IN_5") (pintype "unspecified"))
      (node (ref "U5") (pin "6") (pinfunction "IN_6") (pintype "unspecified"))
      (node (ref "U5") (pin "7") (pinfunction "IN_7") (pintype "unspecified"))
      (node (ref "U5") (pin "8") (pinfunction "IN_8") (pintype "unspecified"))
      (node (ref "U6") (pin "10") (pinfunction "BIAS_10") (pintype "unspecified"))
      (node (ref "U6") (pin "5") (pinfunction "IN_5") (pintype "unspecified"))
      (node (ref "U6") (pin "6") (pinfunction "IN_6") (pintype "unspecified"))
      (node (ref "U6") (pin "7") (pinfunction "IN_7") (pintype "unspecified"))
      (node (ref "U6") (pin "8") (pinfunction "IN_8") (pintype "unspecified"))
      (node (ref "U7") (pin "1") (pinfunction "IN_1") (pintype "unspecified"))
      (node (ref "U7") (pin "2") (pinfunction "IN_2") (pintype "unspecified"))
      (node (ref "U7") (pin "4") (pinfunction "BIAS_4") (pintype "unspecified"))
    )
    (net (code "43") (name "VCC_7V") (class "Default")
      (node (ref "C14") (pin "1") (pinfunction "1_1") (pintype "input"))
      (node (ref "C9") (pin "1") (pinfunction "1_1") (pintype "input"))
      (node (ref "CN2") (pin "1") (pinfunction "1_1") (pintype "unspecified"))
      (node (ref "D5") (pin "1") (pinfunction "C_1") (pintype "unspecified"))
      (node (ref "FL3") (pin "3") (pinfunction "OUT_3") (pintype "unspecified"))
      (node (ref "J4") (pin "1") (pinfunction "1_1") (pintype "unspecified"))
      (node (ref "U3") (pin "1") (pinfunction "INPUT_1") (pintype "unspecified"))
    )
    (net (code "44") (name "VCC_12V") (class "Default")
      (node (ref "C2") (pin "1") (pinfunction "1_1") (pintype "unspecified"))
      (node (ref "C4") (pin "1") (pinfunction "1_1") (pintype "input"))
      (node (ref "C8") (pin "1") (pinfunction "1_1") (pintype "input"))
      (node (ref "CN1") (pin "1") (pinfunction "1_1") (pintype "unspecified"))
      (node (ref "J3") (pin "1") (pinfunction "1_1") (pintype "unspecified"))
      (node (ref "L1") (pin "2") (pinfunction "2_2") (pintype "unspecified"))
      (node (ref "R5") (pin "1") (pinfunction "1_1") (pintype "input"))
      (node (ref "U2") (pin "1") (pinfunction "VIN_1") (pintype "unspecified"))
    )
    (net (code "45") (name "unconnected-(U3-COMMON-Pad2)") (class "Default")
      (node (ref "U3") (pin "2") (pinfunction "COMMON_2") (pintype "unspecified"))
    )
  )
)
